# Moteino.net
KiCad netlist of a schematic drawn in EAGLE
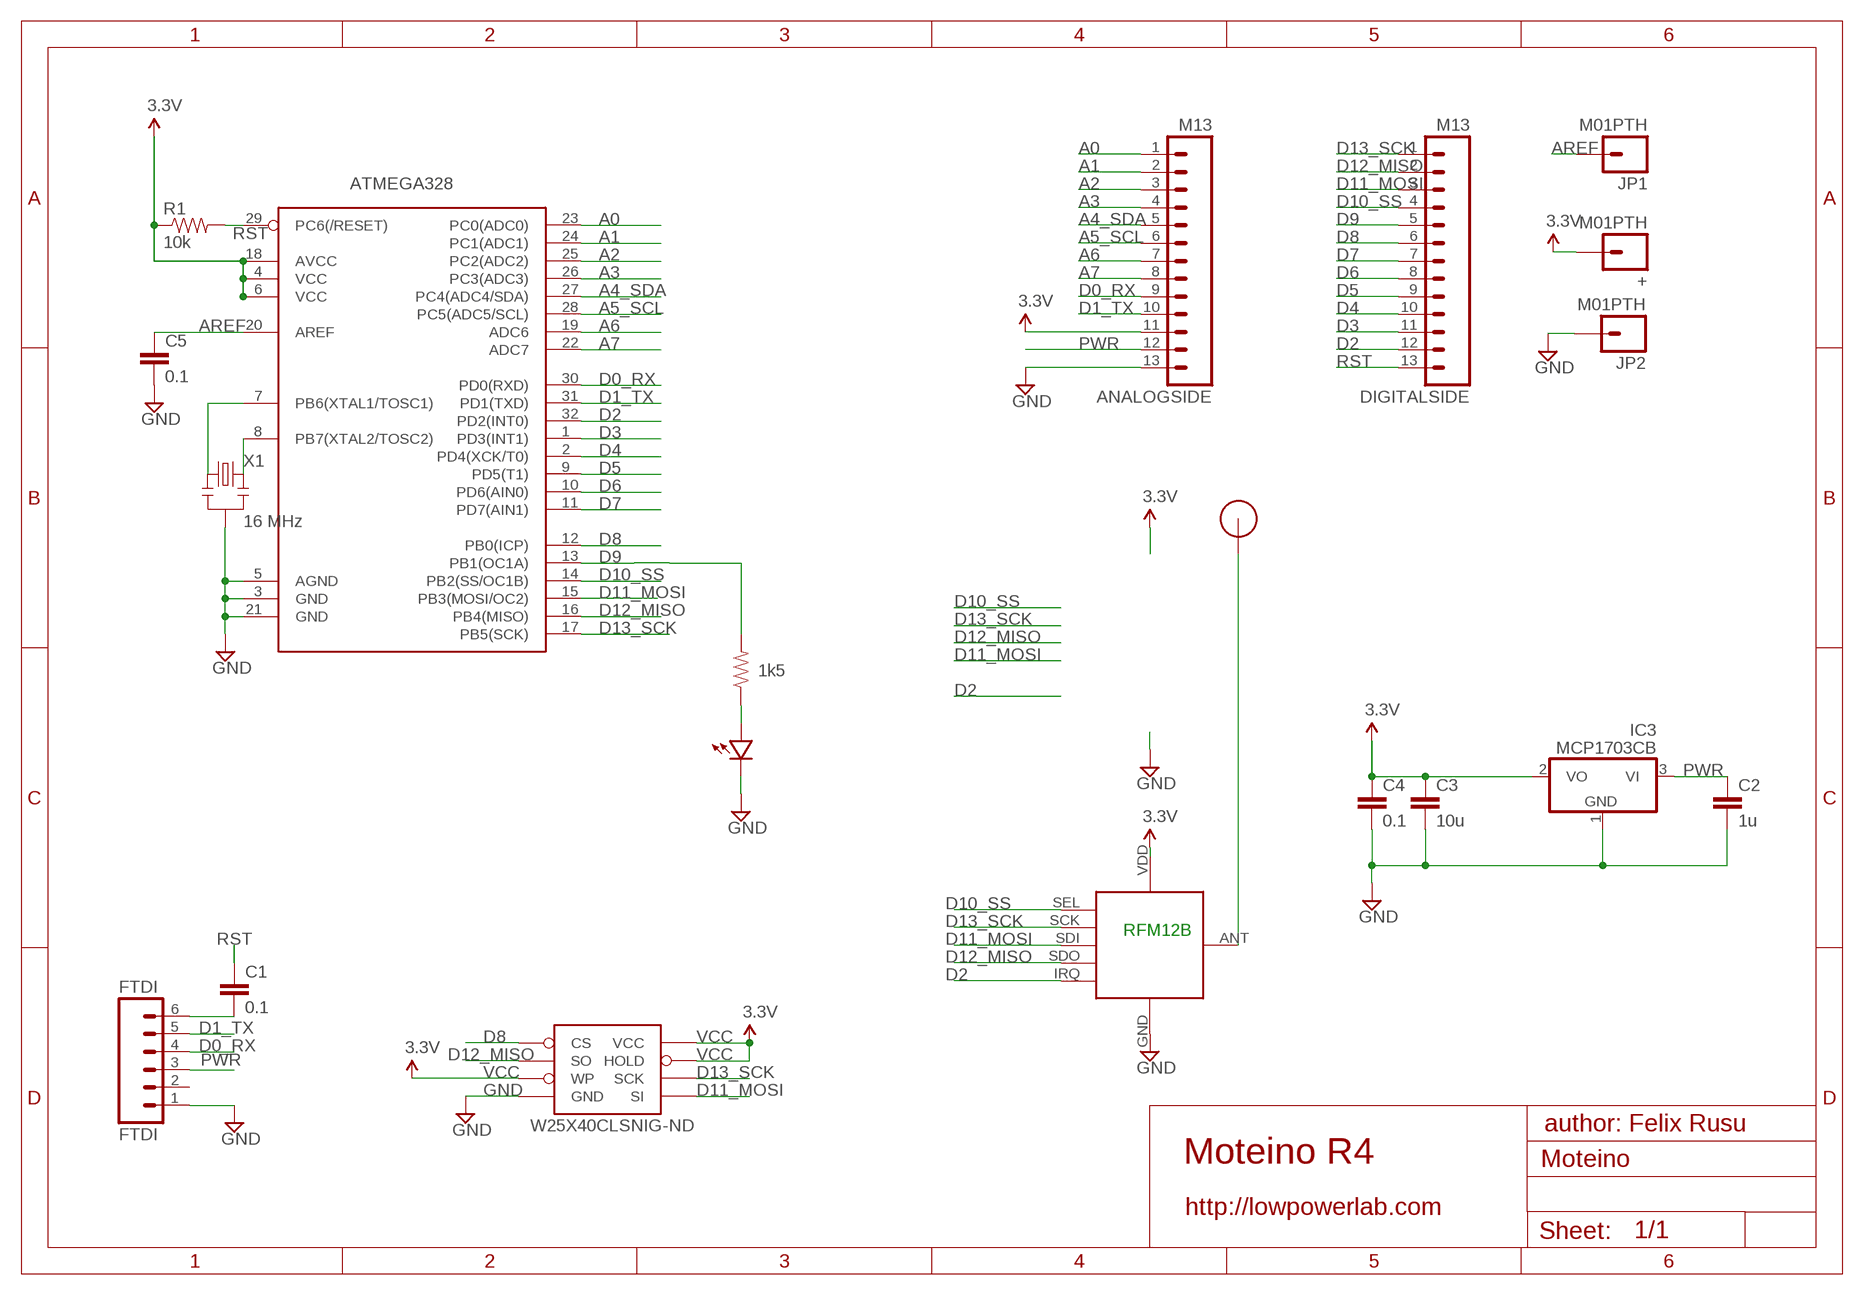
[diagram p0: schematic, sheet 1]

(export (version "E")
  (design (tool "Eeschema 10.0.6"))
  (components
    (comp (ref "+")
      (value "M01PTH")
      (footprint "eagle-import:1X01")
      (libsource (lib "eagle-import") (part "M01PTH"))
    )
    (comp (ref "ANALOGSIDE")
      (value "M13")
      (footprint "eagle-import:1X13")
      (libsource (lib "eagle-import") (part "M13"))
    )
    (comp (ref "ATMEGA328")
      (value "ATMega-328")
      (footprint "eagle-import:TQFP32-08")
      (libsource (lib "eagle-import") (part "ATMEGA168/328TQFP32"))
    )
    (comp (ref "C1")
      (value "0.1")
      (footprint "eagle-import:0603-CAP")
      (libsource (lib "eagle-import") (part "CAP0603-CAP"))
    )
    (comp (ref "C2")
      (value "1u")
      (footprint "eagle-import:0603-CAP")
      (libsource (lib "eagle-import") (part "CAP0603-CAP"))
    )
    (comp (ref "C3")
      (value "10u")
      (footprint "eagle-import:0805-CAP")
      (libsource (lib "eagle-import") (part "CAP0805-CAP"))
    )
    (comp (ref "C4")
      (value "0.1")
      (footprint "eagle-import:0603-CAP")
      (libsource (lib "eagle-import") (part "CAP0603-CAP"))
    )
    (comp (ref "C5")
      (value "0.1")
      (footprint "eagle-import:0603-CAP")
      (libsource (lib "eagle-import") (part "CAP0603-CAP"))
    )
    (comp (ref "DIGITALSIDE")
      (value "M13")
      (footprint "eagle-import:1X13")
      (libsource (lib "eagle-import") (part "M13"))
    )
    (comp (ref "FTDI")
      (value "FTDI")
      (footprint "eagle-import:1X06")
      (libsource (lib "eagle-import") (part "M06SIP"))
    )
    (comp (ref "IC3")
      (value "MCP1703CB")
      (footprint "eagle-import:SOT23")
      (libsource (lib "eagle-import") (part "MCP1703CB"))
    )
    (comp (ref "JP1")
      (value "M01PTH")
      (footprint "eagle-import:1X01")
      (libsource (lib "eagle-import") (part "M01PTH"))
    )
    (comp (ref "JP2")
      (value "M01PTH")
      (footprint "eagle-import:1X01")
      (libsource (lib "eagle-import") (part "M01PTH"))
    )
    (comp (ref "R1")
      (value "10k")
      (footprint "eagle-import:0603-RES")
      (libsource (lib "eagle-import") (part "RESISTOR0603-RES"))
    )
    (comp (ref "R2")
      (value "1k5")
      (footprint "eagle-import:0603-RES")
      (libsource (lib "eagle-import") (part "RESISTOR0603-RES"))
    )
    (comp (ref "RFM12B")
      (value "RFM12B_MINPADS")
      (footprint "eagle-import:RFM12B-MINPADS")
      (libsource (lib "eagle-import") (part "RFM12B_MINPADS"))
    )
    (comp (ref "U$1")
      (value "RFM12B_ANTENNA")
      (footprint "eagle-import:RFM12B-ANTENNA")
      (libsource (lib "eagle-import") (part "RFM12B_ANTENNA"))
    )
    (comp (ref "U$2")
      (value "LED0603")
      (footprint "eagle-import:0603-LED")
      (libsource (lib "eagle-import") (part "LED0603"))
    )
    (comp (ref "W25X40CLSNIG-ND")
      (value "AT25F512BWIDE_5.3MM")
      (footprint "eagle-import:SO08WIDE")
      (libsource (lib "eagle-import") (part "AT25F512BWIDE_5.3MM"))
    )
    (comp (ref "X1")
      (value "16 MHz")
      (footprint "eagle-import:RESONATOR-SMD")
      (libsource (lib "eagle-import") (part "RESONATORSMD"))
    )
  )
  (nets
    (net (code "1") (name "/A0") (class "Default")
      (node (ref "ANALOGSIDE") (pin "1") (pinfunction "1_1") (pintype "passive"))
      (node (ref "ATMEGA328") (pin "23") (pinfunction "PC0(ADC0)_23") (pintype "bidirectional"))
    )
    (net (code "2") (name "/A1") (class "Default")
      (node (ref "ANALOGSIDE") (pin "2") (pinfunction "2_2") (pintype "passive"))
      (node (ref "ATMEGA328") (pin "24") (pinfunction "PC1(ADC1)_24") (pintype "bidirectional"))
    )
    (net (code "3") (name "/A2") (class "Default")
      (node (ref "ANALOGSIDE") (pin "3") (pinfunction "3_3") (pintype "passive"))
      (node (ref "ATMEGA328") (pin "25") (pinfunction "PC2(ADC2)_25") (pintype "bidirectional"))
    )
    (net (code "4") (name "/A3") (class "Default")
      (node (ref "ANALOGSIDE") (pin "4") (pinfunction "4_4") (pintype "passive"))
      (node (ref "ATMEGA328") (pin "26") (pinfunction "PC3(ADC3)_26") (pintype "bidirectional"))
    )
    (net (code "5") (name "/A4_SDA") (class "Default")
      (node (ref "ANALOGSIDE") (pin "5") (pinfunction "5_5") (pintype "passive"))
      (node (ref "ATMEGA328") (pin "27") (pinfunction "PC4(ADC4/SDA)_27") (pintype "bidirectional"))
    )
    (net (code "6") (name "/A5_SCL") (class "Default")
      (node (ref "ANALOGSIDE") (pin "6") (pinfunction "6_6") (pintype "passive"))
      (node (ref "ATMEGA328") (pin "28") (pinfunction "PC5(ADC5/SCL)_28") (pintype "bidirectional"))
    )
    (net (code "7") (name "/A6") (class "Default")
      (node (ref "ANALOGSIDE") (pin "7") (pinfunction "7_7") (pintype "passive"))
      (node (ref "ATMEGA328") (pin "19") (pinfunction "ADC6_19") (pintype "bidirectional"))
    )
    (net (code "8") (name "/A7") (class "Default")
      (node (ref "ANALOGSIDE") (pin "8") (pinfunction "8_8") (pintype "passive"))
      (node (ref "ATMEGA328") (pin "22") (pinfunction "ADC7_22") (pintype "bidirectional"))
    )
    (net (code "9") (name "/AREF") (class "Default")
      (node (ref "ATMEGA328") (pin "20") (pinfunction "AREF_20") (pintype "bidirectional"))
      (node (ref "C5") (pin "1") (pinfunction "1_1") (pintype "passive"))
      (node (ref "JP1") (pin "1") (pinfunction "1_1") (pintype "passive"))
    )
    (net (code "10") (name "/D0_RX") (class "Default")
      (node (ref "ANALOGSIDE") (pin "9") (pinfunction "9_9") (pintype "passive"))
      (node (ref "ATMEGA328") (pin "30") (pinfunction "PD0(RXD)_30") (pintype "bidirectional"))
      (node (ref "FTDI") (pin "4") (pinfunction "4_4") (pintype "passive"))
    )
    (net (code "11") (name "/D1_TX") (class "Default")
      (node (ref "ANALOGSIDE") (pin "10") (pinfunction "10_10") (pintype "passive"))
      (node (ref "ATMEGA328") (pin "31") (pinfunction "PD1(TXD)_31") (pintype "bidirectional"))
      (node (ref "FTDI") (pin "5") (pinfunction "5_5") (pintype "passive"))
    )
    (net (code "12") (name "/D2") (class "Default")
      (node (ref "ATMEGA328") (pin "32") (pinfunction "PD2(INT0)_32") (pintype "bidirectional"))
      (node (ref "DIGITALSIDE") (pin "12") (pinfunction "12_12") (pintype "passive"))
      (node (ref "RFM12B") (pin "IRQ") (pinfunction "IRQ_IRQ") (pintype "bidirectional"))
    )
    (net (code "13") (name "/D3") (class "Default")
      (node (ref "ATMEGA328") (pin "1") (pinfunction "PD3(INT1)_1") (pintype "bidirectional"))
      (node (ref "DIGITALSIDE") (pin "11") (pinfunction "11_11") (pintype "passive"))
    )
    (net (code "14") (name "/D4") (class "Default")
      (node (ref "ATMEGA328") (pin "2") (pinfunction "PD4(XCK/T0)_2") (pintype "bidirectional"))
      (node (ref "DIGITALSIDE") (pin "10") (pinfunction "10_10") (pintype "passive"))
    )
    (net (code "15") (name "/D5") (class "Default")
      (node (ref "ATMEGA328") (pin "9") (pinfunction "PD5(T1)_9") (pintype "bidirectional"))
      (node (ref "DIGITALSIDE") (pin "9") (pinfunction "9_9") (pintype "passive"))
    )
    (net (code "16") (name "/D6") (class "Default")
      (node (ref "ATMEGA328") (pin "10") (pinfunction "PD6(AIN0)_10") (pintype "bidirectional"))
      (node (ref "DIGITALSIDE") (pin "8") (pinfunction "8_8") (pintype "passive"))
    )
    (net (code "17") (name "/D7") (class "Default")
      (node (ref "ATMEGA328") (pin "11") (pinfunction "PD7(AIN1)_11") (pintype "bidirectional"))
      (node (ref "DIGITALSIDE") (pin "7") (pinfunction "7_7") (pintype "passive"))
    )
    (net (code "18") (name "/D8") (class "Default")
      (node (ref "ATMEGA328") (pin "12") (pinfunction "PB0(ICP)_12") (pintype "bidirectional"))
      (node (ref "DIGITALSIDE") (pin "6") (pinfunction "6_6") (pintype "passive"))
      (node (ref "W25X40CLSNIG-ND") (pin "1") (pinfunction "CS_1") (pintype "bidirectional"))
    )
    (net (code "19") (name "/D9") (class "Default")
      (node (ref "ATMEGA328") (pin "13") (pinfunction "PB1(OC1A)_13") (pintype "bidirectional"))
      (node (ref "DIGITALSIDE") (pin "5") (pinfunction "5_5") (pintype "passive"))
      (node (ref "R2") (pin "2") (pinfunction "2_2") (pintype "passive"))
    )
    (net (code "20") (name "/D10_SS") (class "Default")
      (node (ref "ATMEGA328") (pin "14") (pinfunction "PB2(SS/OC1B)_14") (pintype "bidirectional"))
      (node (ref "DIGITALSIDE") (pin "4") (pinfunction "4_4") (pintype "passive"))
      (node (ref "RFM12B") (pin "SEL") (pinfunction "SEL_SEL") (pintype "bidirectional"))
    )
    (net (code "21") (name "/D11_MOSI") (class "Default")
      (node (ref "ATMEGA328") (pin "15") (pinfunction "PB3(MOSI/OC2)_15") (pintype "bidirectional"))
      (node (ref "DIGITALSIDE") (pin "3") (pinfunction "3_3") (pintype "passive"))
      (node (ref "RFM12B") (pin "SDI") (pinfunction "SDI/MOSI_SDI") (pintype "bidirectional"))
      (node (ref "W25X40CLSNIG-ND") (pin "5") (pinfunction "SI_5") (pintype "bidirectional"))
    )
    (net (code "22") (name "/D12_MISO") (class "Default")
      (node (ref "ATMEGA328") (pin "16") (pinfunction "PB4(MISO)_16") (pintype "bidirectional"))
      (node (ref "DIGITALSIDE") (pin "2") (pinfunction "2_2") (pintype "passive"))
      (node (ref "RFM12B") (pin "SDO") (pinfunction "SDO/MISO_SDO") (pintype "bidirectional"))
      (node (ref "W25X40CLSNIG-ND") (pin "2") (pinfunction "SO_2") (pintype "bidirectional"))
    )
    (net (code "23") (name "/D13_SCK") (class "Default")
      (node (ref "ATMEGA328") (pin "17") (pinfunction "PB5(SCK)_17") (pintype "bidirectional"))
      (node (ref "DIGITALSIDE") (pin "1") (pinfunction "1_1") (pintype "passive"))
      (node (ref "RFM12B") (pin "SCK") (pinfunction "SCK_SCK") (pintype "bidirectional"))
      (node (ref "W25X40CLSNIG-ND") (pin "6") (pinfunction "SCK_6") (pintype "bidirectional"))
    )
    (net (code "24") (name "/PWR") (class "Default")
      (node (ref "ANALOGSIDE") (pin "12") (pinfunction "12_12") (pintype "passive"))
      (node (ref "C2") (pin "1") (pinfunction "1_1") (pintype "passive"))
      (node (ref "FTDI") (pin "3") (pinfunction "3_3") (pintype "passive"))
      (node (ref "IC3") (pin "3") (pinfunction "VI_3") (pintype "input"))
    )
    (net (code "25") (name "/RST") (class "Default")
      (node (ref "ATMEGA328") (pin "29") (pinfunction "PC6(/RESET)_29") (pintype "bidirectional"))
      (node (ref "C1") (pin "1") (pinfunction "1_1") (pintype "passive"))
      (node (ref "DIGITALSIDE") (pin "13") (pinfunction "13_13") (pintype "passive"))
      (node (ref "R1") (pin "2") (pinfunction "2_2") (pintype "passive"))
    )
    (net (code "26") (name "3.3V") (class "Default")
      (node (ref "+") (pin "1") (pinfunction "1_1") (pintype "passive"))
      (node (ref "ANALOGSIDE") (pin "11") (pinfunction "11_11") (pintype "passive"))
      (node (ref "ATMEGA328") (pin "18") (pinfunction "AVCC_18") (pintype "bidirectional"))
      (node (ref "ATMEGA328") (pin "4") (pinfunction "VCC_4") (pintype "bidirectional"))
      (node (ref "ATMEGA328") (pin "6") (pinfunction "VCC_6") (pintype "bidirectional"))
      (node (ref "C3") (pin "1") (pinfunction "1_1") (pintype "passive"))
      (node (ref "C4") (pin "1") (pinfunction "1_1") (pintype "passive"))
      (node (ref "IC3") (pin "2") (pinfunction "VO_2") (pintype "passive"))
      (node (ref "R1") (pin "1") (pinfunction "1_1") (pintype "passive"))
      (node (ref "RFM12B") (pin "VDD") (pinfunction "VDD_VDD") (pintype "bidirectional"))
      (node (ref "W25X40CLSNIG-ND") (pin "3") (pinfunction "WP_3") (pintype "bidirectional"))
      (node (ref "W25X40CLSNIG-ND") (pin "7") (pinfunction "HOLD_7") (pintype "bidirectional"))
      (node (ref "W25X40CLSNIG-ND") (pin "8") (pinfunction "VCC_8") (pintype "bidirectional"))
    )
    (net (code "27") (name "GND") (class "Default")
      (node (ref "ANALOGSIDE") (pin "13") (pinfunction "13_13") (pintype "passive"))
      (node (ref "ATMEGA328") (pin "21") (pinfunction "GND_21") (pintype "bidirectional"))
      (node (ref "ATMEGA328") (pin "3") (pinfunction "GND_3") (pintype "bidirectional"))
      (node (ref "ATMEGA328") (pin "5") (pinfunction "AGND_5") (pintype "bidirectional"))
      (node (ref "C2") (pin "2") (pinfunction "2_2") (pintype "passive"))
      (node (ref "C3") (pin "2") (pinfunction "2_2") (pintype "passive"))
      (node (ref "C4") (pin "2") (pinfunction "2_2") (pintype "passive"))
      (node (ref "C5") (pin "2") (pinfunction "2_2") (pintype "passive"))
      (node (ref "FTDI") (pin "1") (pinfunction "1_1") (pintype "passive"))
      (node (ref "IC3") (pin "1") (pinfunction "GND_1") (pintype "passive"))
      (node (ref "JP2") (pin "1") (pinfunction "1_1") (pintype "passive"))
      (node (ref "RFM12B") (pin "GND") (pinfunction "GND_GND") (pintype "bidirectional"))
      (node (ref "U$2") (pin "MINUS") (pinfunction "MINUS_MINUS") (pintype "passive"))
      (node (ref "W25X40CLSNIG-ND") (pin "4") (pinfunction "GND_4") (pintype "bidirectional"))
      (node (ref "X1") (pin "2") (pinfunction "2_2") (pintype "passive"))
    )
    (net (code "28") (name "Net-(ATMEGA328-PB6(XTAL1{slash}TOSC1))") (class "Default")
      (node (ref "ATMEGA328") (pin "7") (pinfunction "PB6(XTAL1/TOSC1)_7") (pintype "bidirectional"))
      (node (ref "X1") (pin "1") (pinfunction "1_1") (pintype "passive"))
    )
    (net (code "29") (name "Net-(ATMEGA328-PB7(XTAL2{slash}TOSC2))") (class "Default")
      (node (ref "ATMEGA328") (pin "8") (pinfunction "PB7(XTAL2/TOSC2)_8") (pintype "bidirectional"))
      (node (ref "X1") (pin "3") (pinfunction "3_3") (pintype "passive"))
    )
    (net (code "30") (name "Net-(C1-Pad2)") (class "Default")
      (node (ref "C1") (pin "2") (pinfunction "2_2") (pintype "passive"))
      (node (ref "FTDI") (pin "6") (pinfunction "6_6") (pintype "passive"))
    )
    (net (code "31") (name "Net-(R2-Pad1)") (class "Default")
      (node (ref "R2") (pin "1") (pinfunction "1_1") (pintype "passive"))
      (node (ref "U$2") (pin "PLUS") (pinfunction "PLUS_PLUS") (pintype "passive"))
    )
    (net (code "32") (name "Net-(U$1-1)") (class "Default")
      (node (ref "RFM12B") (pin "ANT") (pinfunction "ANT_ANT") (pintype "bidirectional"))
      (node (ref "U$1") (pin "P$1") (pinfunction "1_P$1") (pintype "bidirectional"))
    )
    (net (code "33") (name "unconnected-(FTDI-Pad2)") (class "Default")
      (node (ref "FTDI") (pin "2") (pinfunction "2_2") (pintype "passive"))
    )
  )
)
